# X-Track-ESP32.net
KiCad netlist of a schematic drawn in Altium Designer
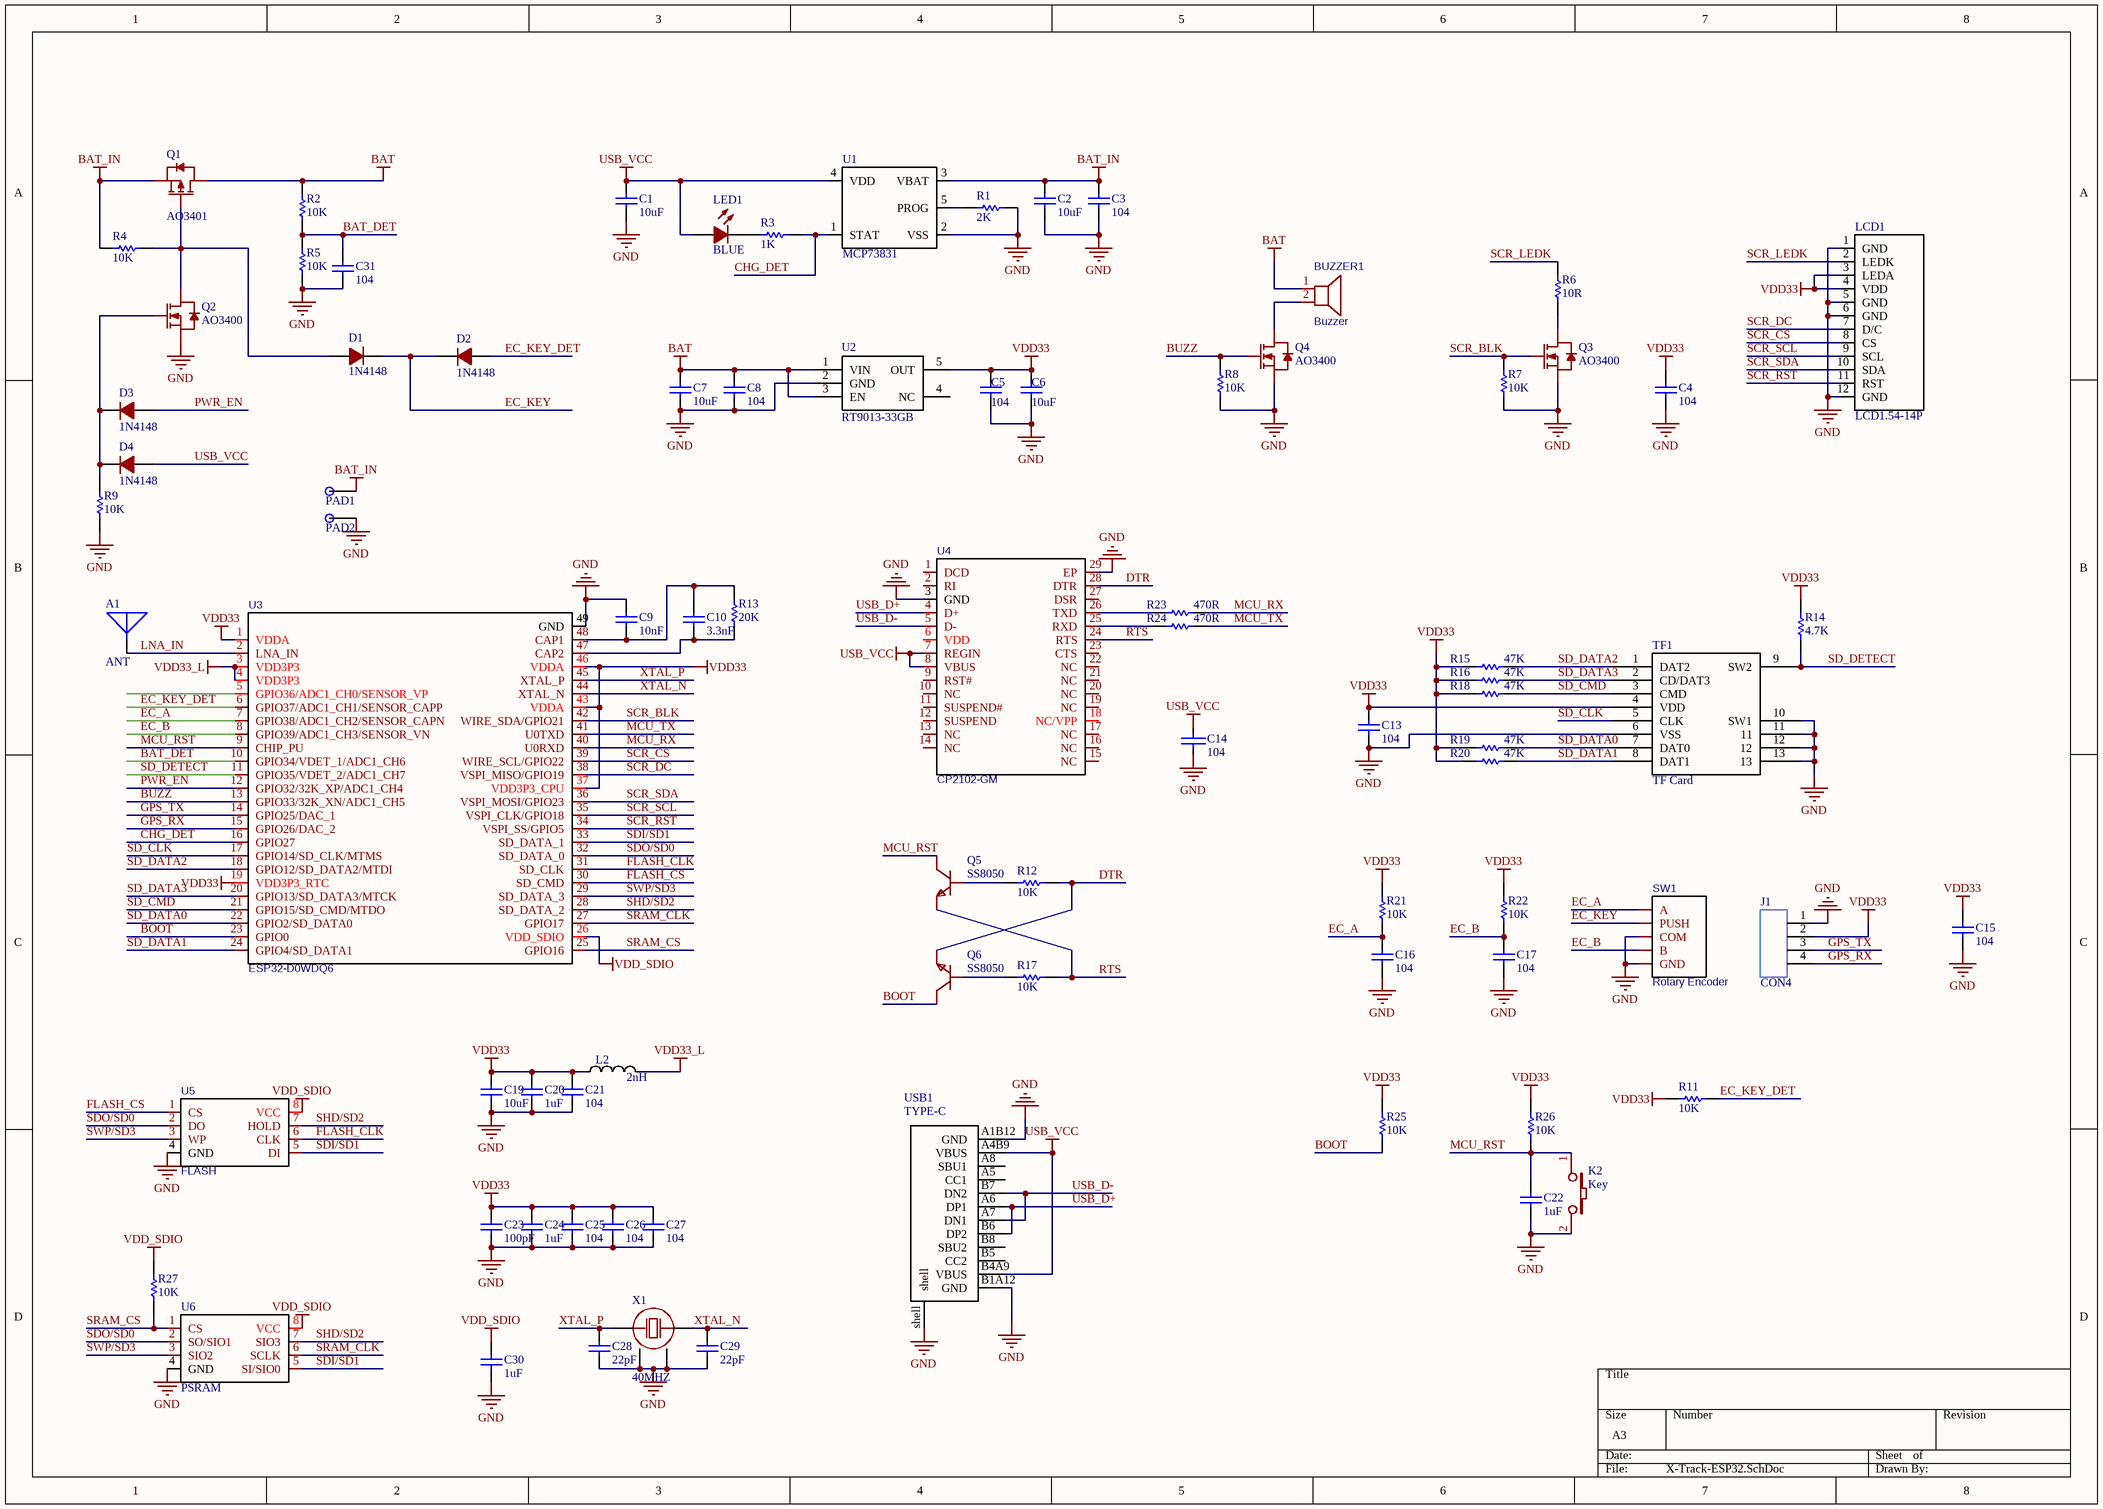
[diagram p0: X-Track-ESP32.SchDoc]

(export (version "E")
  (design (tool "Eeschema 10.0.6"))
  (components
    (comp (ref "A1") (value "ANT") (footprint "ANT-Rainsun-AN5120") (libsource (lib "mylib") (part "ANT")))
    (comp (ref "BUZZER1")
      (value "Buzzer")
      (footprint "BUZZ-SMD_5020")
      (fields
        (field (name "BOM_SUPPLIER PART") "C360618")
        (field (name "BOM_MANUFACTURER PART") "SFN-1207PA6.5")
        (field (name "CONTRIBUTOR") "LCSC")
      )
      (libsource (lib "mylib") (part "Buzzer"))
    )
    (comp (ref "C1") (value "10uF") (footprint "C 0402") (libsource (lib "Sheet") (part "CAP")))
    (comp (ref "C2") (value "10uF") (footprint "C 0402") (libsource (lib "Sheet") (part "CAP")))
    (comp (ref "C3") (value "104") (footprint "C 0402") (libsource (lib "Sheet") (part "CAP")))
    (comp (ref "C4") (value "104") (footprint "C 0402") (libsource (lib "mylib") (part "CAP")))
    (comp (ref "C5") (value "104") (footprint "C 0402") (libsource (lib "Sheet") (part "CAP")))
    (comp (ref "C6") (value "10uF") (footprint "C 0402") (libsource (lib "Sheet") (part "CAP")))
    (comp (ref "C7") (value "10uF") (footprint "C 0402") (libsource (lib "Sheet") (part "CAP")))
    (comp (ref "C8") (value "104") (footprint "C 0402") (libsource (lib "Sheet") (part "CAP")))
    (comp (ref "C9") (value "10nF") (footprint "C 0402") (libsource (lib "mylib") (part "CAP")))
    (comp (ref "C10") (value "3.3nF") (footprint "C 0402") (libsource (lib "mylib") (part "CAP")))
    (comp (ref "C13")
      (value "104")
      (footprint "C 0402")
      (description "Capacitor")
      (libsource (lib "Miscellaneous Devices") (part "Cap"))
    )
    (comp (ref "C14")
      (value "104")
      (footprint "C 0402")
      (description "Capacitor")
      (libsource (lib "*") (part "CAP"))
    )
    (comp (ref "C15") (value "104") (footprint "C 0402") (libsource (lib "mylib") (part "CAP")))
    (comp (ref "C16")
      (value "104")
      (footprint "C 0402")
      (description "Capacitor")
      (libsource (lib "Miscellaneous Devices") (part "Cap"))
    )
    (comp (ref "C17")
      (value "104")
      (footprint "C 0402")
      (description "Capacitor")
      (libsource (lib "Miscellaneous Devices") (part "Cap"))
    )
    (comp (ref "C19") (value "10uF") (footprint "C 0402") (libsource (lib "mylib") (part "CAP")))
    (comp (ref "C20") (value "1uF") (footprint "C 0402") (libsource (lib "mylib") (part "CAP")))
    (comp (ref "C21") (value "104") (footprint "C 0402") (libsource (lib "mylib") (part "CAP")))
    (comp (ref "C22")
      (value "1uF")
      (footprint "C 0402")
      (description "Capacitor")
      (libsource (lib "Miscellaneous Devices") (part "Cap"))
    )
    (comp (ref "C23") (value "100pF") (footprint "C 0402") (libsource (lib "mylib") (part "CAP")))
    (comp (ref "C24") (value "1uF") (footprint "C 0402") (libsource (lib "mylib") (part "CAP")))
    (comp (ref "C25") (value "104") (footprint "C 0402") (libsource (lib "mylib") (part "CAP")))
    (comp (ref "C26") (value "104") (footprint "C 0402") (libsource (lib "mylib") (part "CAP")))
    (comp (ref "C27") (value "104") (footprint "C 0402") (libsource (lib "mylib") (part "CAP")))
    (comp (ref "C28") (value "22pF") (footprint "C 0402") (libsource (lib "mylib") (part "CAP")))
    (comp (ref "C29") (value "22pF") (footprint "C 0402") (libsource (lib "mylib") (part "CAP")))
    (comp (ref "C30") (value "1uF") (footprint "C 0402") (libsource (lib "mylib") (part "CAP")))
    (comp (ref "C31") (value "104") (footprint "C 0402") (libsource (lib "Sheet") (part "CAP")))
    (comp (ref "D1") (value "1N4148") (footprint "SOD523") (libsource (lib "mylib") (part "Diode")))
    (comp (ref "D2") (value "1N4148") (footprint "SOD523") (libsource (lib "mylib") (part "Diode")))
    (comp (ref "D3") (value "1N4148") (footprint "SOD523") (libsource (lib "mylib") (part "Diode")))
    (comp (ref "D4") (value "1N4148") (footprint "SOD523") (libsource (lib "mylib") (part "Diode")))
    (comp (ref "J1") (value "CON4") (footprint "GPS-HTZN") (libsource (lib "mylib") (part "CON4")))
    (comp (ref "K2") (value "Key") (footprint "SW-SMD_3*4") (libsource (lib "mylib") (part "Key")))
    (comp (ref "L2") (value "2nH") (footprint "L 0402") (libsource (lib "mylib") (part "Inductor")))
    (comp (ref "LCD1")
      (value "LCD1.54-14P")
      (footprint "ZJY154T-PG04 FPC 0.7MM")
      (libsource (lib "mylib") (part "LCD1.54-14P_1"))
    )
    (comp (ref "LED1") (value "BLUE") (footprint "LED 0603") (libsource (lib "mylib") (part "LED")))
    (comp (ref "PAD1") (value "PAD") (footprint "PAD") (libsource (lib "mylib") (part "PAD")))
    (comp (ref "PAD2") (value "PAD") (footprint "PAD") (libsource (lib "mylib") (part "PAD")))
    (comp (ref "Q1") (value "AO3401") (footprint "SOT-23") (libsource (lib "mylib") (part "PMOS")))
    (comp (ref "Q2") (value "AO3400") (footprint "SOT-23") (libsource (lib "mylib") (part "NMOS")))
    (comp (ref "Q3") (value "AO3400") (footprint "SOT-23") (libsource (lib "mylib") (part "NMOS")))
    (comp (ref "Q4") (value "AO3400") (footprint "SOT-23") (libsource (lib "mylib") (part "NMOS")))
    (comp (ref "Q5") (value "SS8050") (footprint "SOT-23") (libsource (lib "mylib") (part "NPN")))
    (comp (ref "Q6") (value "SS8050") (footprint "SOT-23") (libsource (lib "mylib") (part "NPN")))
    (comp (ref "R1") (value "2K") (footprint "R 0402") (libsource (lib "Sheet") (part "RES")))
    (comp (ref "R2") (value "10K") (footprint "R 0402") (libsource (lib "mylib") (part "RES")))
    (comp (ref "R3") (value "1K") (footprint "R 0402") (libsource (lib "Sheet") (part "RES")))
    (comp (ref "R4") (value "10K") (footprint "R 0402") (libsource (lib "mylib") (part "RES")))
    (comp (ref "R5") (value "10K") (footprint "R 0402") (libsource (lib "mylib") (part "RES")))
    (comp (ref "R6") (value "10R") (footprint "R 0402") (libsource (lib "Sheet") (part "RES")))
    (comp (ref "R7") (value "10K") (footprint "R 0402") (libsource (lib "Sheet") (part "RES")))
    (comp (ref "R8") (value "10K") (footprint "R 0402") (libsource (lib "Sheet") (part "RES")))
    (comp (ref "R9") (value "10K") (footprint "R 0402") (libsource (lib "mylib") (part "RES")))
    (comp (ref "R11") (value "10K") (footprint "R 0402") (libsource (lib "Sheet") (part "RES")))
    (comp (ref "R12") (value "10K") (footprint "R 0402") (libsource (lib "Sheet") (part "RES")))
    (comp (ref "R13") (value "20K") (footprint "R 0402") (libsource (lib "mylib") (part "RES")))
    (comp (ref "R14") (value "4.7K") (footprint "R 0402") (libsource (lib "Sheet") (part "RES")))
    (comp (ref "R15") (value "47K") (footprint "R 0402") (libsource (lib "Sheet") (part "RES")))
    (comp (ref "R16") (value "47K") (footprint "R 0402") (libsource (lib "Sheet") (part "RES")))
    (comp (ref "R17") (value "10K") (footprint "R 0402") (libsource (lib "Sheet") (part "RES")))
    (comp (ref "R18") (value "47K") (footprint "R 0402") (libsource (lib "Sheet") (part "RES")))
    (comp (ref "R19") (value "47K") (footprint "R 0402") (libsource (lib "Sheet") (part "RES")))
    (comp (ref "R20") (value "47K") (footprint "R 0402") (libsource (lib "Sheet") (part "RES")))
    (comp (ref "R21") (value "10K") (footprint "R 0402") (libsource (lib "Sheet") (part "RES")))
    (comp (ref "R22") (value "10K") (footprint "R 0402") (libsource (lib "Sheet") (part "RES")))
    (comp (ref "R23") (value "470R") (footprint "R 0402") (libsource (lib "Sheet") (part "RES")))
    (comp (ref "R24") (value "470R") (footprint "R 0402") (libsource (lib "Sheet") (part "RES")))
    (comp (ref "R25") (value "10K") (footprint "R 0402") (libsource (lib "Sheet") (part "RES")))
    (comp (ref "R26") (value "10K") (footprint "R 0402") (libsource (lib "Sheet") (part "RES")))
    (comp (ref "R27") (value "10K") (footprint "R 0402") (libsource (lib "mylib") (part "RES")))
    (comp (ref "SW1")
      (value "Rotary Encoder")
      (footprint "SIQ-02FVS3")
      (fields
        (field (name "BOM_SUPPLIER PART") "C1322543")
        (field (name "BOM_MANUFACTURER PART") "EC11E1534443")
        (field (name "CONTRIBUTOR") "LCSC")
      )
      (libsource (lib "mylib") (part "Rotary Encoder"))
    )
    (comp (ref "TF1") (value "TF Card") (footprint "TF-Card") (libsource (lib "mylib") (part "TF Card")))
    (comp (ref "U1") (value "MCP73831") (footprint "SOT23-5") (libsource (lib "mylib") (part "MCP73831")))
    (comp (ref "U2") (value "RT9013-33GB") (footprint "SOT23-5") (libsource (lib "mylib") (part "SPX3819")))
    (comp (ref "U3")
      (value "ESP32-D0WDQ6")
      (footprint "QFN-48")
      (fields (field (name "BOM_SUPPLIER PART") "C129733") (field (name "CONTRIBUTOR") "LCSC"))
      (libsource (lib "mylib") (part "ESP32-D0WDQ6"))
    )
    (comp (ref "U4")
      (value "CP2102-GM")
      (footprint "QFN-28")
      (fields (field (name "BOM_SUPPLIER PART") "C430012") (field (name "CONTRIBUTOR") "LCSC"))
      (libsource (lib "mylib") (part "CP2102-GM"))
    )
    (comp (ref "U5")
      (value "FLASH")
      (footprint "SOIC-8")
      (fields
        (field (name "BOM_SUPPLIER PART") "C179173")
        (field (name "BOM_MANUFACTURER PART") "W25Q32JVSSIQ")
        (field (name "CONTRIBUTOR") "LCSC")
      )
      (libsource (lib "mylib") (part "FLASH"))
    )
    (comp (ref "U6") (value "PSRAM") (footprint "SOP-8") (libsource (lib "mylib") (part "PSRAM")))
    (comp (ref "USB1")
      (value "TYPE-C")
      (footprint "USB-TYPE-C")
      (description "TYPE-C 16pin")
      (libsource (lib "Sheet") (part "USB TYPE-C"))
    )
    (comp (ref "X1") (value "40MHZ") (footprint "SMD-3225") (libsource (lib "mylib") (part "XTAL-4P")))
  )
  (nets
    (net (code "1") (name "/BAT_DET") (class "Default")
      (node (ref "C31") (pin "2") (pinfunction "2_2") (pintype "passive"))
      (node (ref "R2") (pin "1") (pinfunction "1_1") (pintype "passive"))
      (node (ref "R5") (pin "2") (pinfunction "2_2") (pintype "passive"))
      (node (ref "U3") (pin "10") (pinfunction "GPIO34/VDET_1/ADC1_CH6_10") (pintype "passive"))
    )
    (net (code "2") (name "/BOOT") (class "Default")
      (node (ref "Q6") (pin "3") (pinfunction "C_3") (pintype "passive"))
      (node (ref "R25") (pin "2") (pinfunction "2_2") (pintype "passive"))
      (node (ref "U3") (pin "23") (pinfunction "GPIO0_23") (pintype "passive"))
    )
    (net (code "3") (name "/BUZZ") (class "Default")
      (node (ref "Q4") (pin "1") (pinfunction "G_1") (pintype "passive"))
      (node (ref "R8") (pin "1") (pinfunction "1_1") (pintype "passive"))
      (node (ref "U3") (pin "13") (pinfunction "GPIO33/32K_XN/ADC1_CH5_13") (pintype "passive"))
    )
    (net (code "4") (name "/CHG_DET") (class "Default")
      (node (ref "R3") (pin "1") (pinfunction "1_1") (pintype "passive"))
      (node (ref "U1") (pin "1") (pinfunction "STAT_1") (pintype "passive"))
      (node (ref "U3") (pin "16") (pinfunction "GPIO27_16") (pintype "passive"))
    )
    (net (code "5") (name "/DTR") (class "Default")
      (node (ref "Q6") (pin "2") (pinfunction "E_2") (pintype "passive"))
      (node (ref "R12") (pin "1") (pinfunction "1_1") (pintype "passive"))
      (node (ref "U4") (pin "28") (pinfunction "DTR_28") (pintype "passive"))
    )
    (net (code "6") (name "/EC_A") (class "Default")
      (node (ref "C16") (pin "1") (pinfunction "1_1") (pintype "passive"))
      (node (ref "R21") (pin "2") (pinfunction "2_2") (pintype "passive"))
      (node (ref "SW1") (pin "1") (pinfunction "A_1") (pintype "passive"))
      (node (ref "U3") (pin "7") (pinfunction "GPIO38/ADC1_CH2/SENSOR_CAPN_7") (pintype "passive"))
    )
    (net (code "7") (name "/EC_B") (class "Default")
      (node (ref "C17") (pin "1") (pinfunction "1_1") (pintype "passive"))
      (node (ref "R22") (pin "2") (pinfunction "2_2") (pintype "passive"))
      (node (ref "SW1") (pin "4") (pinfunction "B_4") (pintype "passive"))
      (node (ref "U3") (pin "8") (pinfunction "GPIO39/ADC1_CH3/SENSOR_VN_8") (pintype "passive"))
    )
    (net (code "8") (name "/EC_KEY") (class "Default")
      (node (ref "D1") (pin "2") (pinfunction "C_2") (pintype "passive"))
      (node (ref "D2") (pin "2") (pinfunction "C_2") (pintype "passive"))
      (node (ref "SW1") (pin "2") (pinfunction "PUSH_2") (pintype "passive"))
    )
    (net (code "9") (name "/EC_KEY_DET") (class "Default")
      (node (ref "D2") (pin "1") (pinfunction "A_1") (pintype "passive"))
      (node (ref "R11") (pin "2") (pinfunction "2_2") (pintype "passive"))
      (node (ref "U3") (pin "6") (pinfunction "GPIO37/ADC1_CH1/SENSOR_CAPP_6") (pintype "passive"))
    )
    (net (code "10") (name "/FLASH_CLK") (class "Default")
      (node (ref "U3") (pin "31") (pinfunction "SD_CLK_31") (pintype "passive"))
      (node (ref "U5") (pin "6") (pinfunction "CLK_6") (pintype "passive"))
    )
    (net (code "11") (name "/FLASH_CS") (class "Default")
      (node (ref "U3") (pin "30") (pinfunction "SD_CMD_30") (pintype "passive"))
      (node (ref "U5") (pin "1") (pinfunction "CS_1") (pintype "passive"))
    )
    (net (code "12") (name "/GPS_RX") (class "Default")
      (node (ref "J1") (pin "4") (pinfunction "4_4") (pintype "passive"))
      (node (ref "U3") (pin "15") (pinfunction "GPIO26/DAC_2_15") (pintype "passive"))
    )
    (net (code "13") (name "/GPS_TX") (class "Default")
      (node (ref "J1") (pin "3") (pinfunction "3_3") (pintype "passive"))
      (node (ref "U3") (pin "14") (pinfunction "GPIO25/DAC_1_14") (pintype "passive"))
    )
    (net (code "14") (name "/LNA_IN") (class "Default")
      (node (ref "A1") (pin "1") (pinfunction "1_1") (pintype "passive"))
      (node (ref "U3") (pin "2") (pinfunction "LNA_IN_2") (pintype "passive"))
    )
    (net (code "15") (name "/MCU_RST") (class "Default")
      (node (ref "C22") (pin "1") (pinfunction "1_1") (pintype "passive"))
      (node (ref "K2") (pin "1") (pinfunction "1_1") (pintype "passive"))
      (node (ref "Q5") (pin "3") (pinfunction "C_3") (pintype "passive"))
      (node (ref "R26") (pin "2") (pinfunction "2_2") (pintype "passive"))
      (node (ref "U3") (pin "9") (pinfunction "CHIP_PU_9") (pintype "passive"))
    )
    (net (code "16") (name "/MCU_RX") (class "Default")
      (node (ref "R23") (pin "2") (pinfunction "2_2") (pintype "passive"))
      (node (ref "U3") (pin "40") (pinfunction "U0RXD_40") (pintype "passive"))
    )
    (net (code "17") (name "/MCU_TX") (class "Default")
      (node (ref "R24") (pin "2") (pinfunction "2_2") (pintype "passive"))
      (node (ref "U3") (pin "41") (pinfunction "U0TXD_41") (pintype "passive"))
    )
    (net (code "18") (name "/PWR_EN") (class "Default")
      (node (ref "D3") (pin "1") (pinfunction "A_1") (pintype "passive"))
      (node (ref "U3") (pin "12") (pinfunction "GPIO32/32K_XP/ADC1_CH4_12") (pintype "passive"))
    )
    (net (code "19") (name "/RTS") (class "Default")
      (node (ref "Q5") (pin "2") (pinfunction "E_2") (pintype "passive"))
      (node (ref "R17") (pin "1") (pinfunction "1_1") (pintype "passive"))
      (node (ref "U4") (pin "24") (pinfunction "RTS_24") (pintype "passive"))
    )
    (net (code "20") (name "/SCR_BLK") (class "Default")
      (node (ref "Q3") (pin "1") (pinfunction "G_1") (pintype "passive"))
      (node (ref "R7") (pin "1") (pinfunction "1_1") (pintype "passive"))
      (node (ref "U3") (pin "42") (pinfunction "WIRE_SDA/GPIO21_42") (pintype "passive"))
    )
    (net (code "21") (name "/SCR_CS") (class "Default")
      (node (ref "LCD1") (pin "8") (pinfunction "CS_8") (pintype "passive"))
      (node (ref "U3") (pin "39") (pinfunction "WIRE_SCL/GPIO22_39") (pintype "passive"))
    )
    (net (code "22") (name "/SCR_DC") (class "Default")
      (node (ref "LCD1") (pin "7") (pinfunction "D/C_7") (pintype "passive"))
      (node (ref "U3") (pin "38") (pinfunction "VSPI_MISO/GPIO19_38") (pintype "passive"))
    )
    (net (code "23") (name "/SCR_LEDK") (class "Default")
      (node (ref "LCD1") (pin "2") (pinfunction "LEDK_2") (pintype "passive"))
      (node (ref "R6") (pin "2") (pinfunction "2_2") (pintype "passive"))
    )
    (net (code "24") (name "/SCR_RST") (class "Default")
      (node (ref "LCD1") (pin "11") (pinfunction "RST_11") (pintype "passive"))
      (node (ref "U3") (pin "34") (pinfunction "VSPI_SS/GPIO5_34") (pintype "passive"))
    )
    (net (code "25") (name "/SCR_SCL") (class "Default")
      (node (ref "LCD1") (pin "9") (pinfunction "SCL_9") (pintype "passive"))
      (node (ref "U3") (pin "35") (pinfunction "VSPI_CLK/GPIO18_35") (pintype "passive"))
    )
    (net (code "26") (name "/SCR_SDA") (class "Default")
      (node (ref "LCD1") (pin "10") (pinfunction "SDA_10") (pintype "passive"))
      (node (ref "U3") (pin "36") (pinfunction "VSPI_MOSI/GPIO23_36") (pintype "passive"))
    )
    (net (code "27") (name "/SDI{slash}SD1") (class "Default")
      (node (ref "U3") (pin "33") (pinfunction "SD_DATA_1_33") (pintype "passive"))
      (node (ref "U5") (pin "5") (pinfunction "DI_5") (pintype "passive"))
      (node (ref "U6") (pin "5") (pinfunction "SI/SIO0_5") (pintype "passive"))
    )
    (net (code "28") (name "/SDO{slash}SD0") (class "Default")
      (node (ref "U3") (pin "32") (pinfunction "SD_DATA_0_32") (pintype "passive"))
      (node (ref "U5") (pin "2") (pinfunction "DO_2") (pintype "passive"))
      (node (ref "U6") (pin "2") (pinfunction "SO/SIO1_2") (pintype "passive"))
    )
    (net (code "29") (name "/SD_CLK") (class "Default")
      (node (ref "TF1") (pin "5") (pinfunction "CLK_5") (pintype "passive"))
      (node (ref "U3") (pin "17") (pinfunction "GPIO14/SD_CLK/MTMS_17") (pintype "passive"))
    )
    (net (code "30") (name "/SD_CMD") (class "Default")
      (node (ref "R18") (pin "2") (pinfunction "2_2") (pintype "passive"))
      (node (ref "TF1") (pin "3") (pinfunction "CMD_3") (pintype "passive"))
      (node (ref "U3") (pin "21") (pinfunction "GPIO15/SD_CMD/MTDO_21") (pintype "passive"))
    )
    (net (code "31") (name "/SD_DATA0") (class "Default")
      (node (ref "R19") (pin "2") (pinfunction "2_2") (pintype "passive"))
      (node (ref "TF1") (pin "7") (pinfunction "DAT0_7") (pintype "passive"))
      (node (ref "U3") (pin "22") (pinfunction "GPIO2/SD_DATA0_22") (pintype "passive"))
    )
    (net (code "32") (name "/SD_DATA1") (class "Default")
      (node (ref "R20") (pin "2") (pinfunction "2_2") (pintype "passive"))
      (node (ref "TF1") (pin "8") (pinfunction "DAT1_8") (pintype "passive"))
      (node (ref "U3") (pin "24") (pinfunction "GPIO4/SD_DATA1_24") (pintype "passive"))
    )
    (net (code "33") (name "/SD_DATA2") (class "Default")
      (node (ref "R15") (pin "2") (pinfunction "2_2") (pintype "passive"))
      (node (ref "TF1") (pin "1") (pinfunction "DAT2_1") (pintype "passive"))
      (node (ref "U3") (pin "18") (pinfunction "GPIO12/SD_DATA2/MTDI_18") (pintype "passive"))
    )
    (net (code "34") (name "/SD_DATA3") (class "Default")
      (node (ref "R16") (pin "2") (pinfunction "2_2") (pintype "passive"))
      (node (ref "TF1") (pin "2") (pinfunction "CD/DAT3_2") (pintype "passive"))
      (node (ref "U3") (pin "20") (pinfunction "GPIO13/SD_DATA3/MTCK_20") (pintype "passive"))
    )
    (net (code "35") (name "/SD_DETECT") (class "Default")
      (node (ref "R14") (pin "1") (pinfunction "1_1") (pintype "passive"))
      (node (ref "TF1") (pin "9") (pinfunction "SW2_9") (pintype "passive"))
      (node (ref "U3") (pin "11") (pinfunction "GPIO35/VDET_2/ADC1_CH7_11") (pintype "passive"))
    )
    (net (code "36") (name "/SHD{slash}SD2") (class "Default")
      (node (ref "U3") (pin "28") (pinfunction "SD_DATA_2_28") (pintype "passive"))
      (node (ref "U5") (pin "7") (pinfunction "HOLD_7") (pintype "passive"))
      (node (ref "U6") (pin "7") (pinfunction "SIO3_7") (pintype "passive"))
    )
    (net (code "37") (name "/SRAM_CLK") (class "Default")
      (node (ref "U3") (pin "27") (pinfunction "GPIO17_27") (pintype "passive"))
      (node (ref "U6") (pin "6") (pinfunction "SCLK_6") (pintype "passive"))
    )
    (net (code "38") (name "/SRAM_CS") (class "Default")
      (node (ref "R27") (pin "2") (pinfunction "2_2") (pintype "passive"))
      (node (ref "U3") (pin "25") (pinfunction "GPIO16_25") (pintype "passive"))
      (node (ref "U6") (pin "1") (pinfunction "CS_1") (pintype "passive"))
    )
    (net (code "39") (name "/SWP{slash}SD3") (class "Default")
      (node (ref "U3") (pin "29") (pinfunction "SD_DATA_3_29") (pintype "passive"))
      (node (ref "U5") (pin "3") (pinfunction "WP_3") (pintype "passive"))
      (node (ref "U6") (pin "3") (pinfunction "SIO2_3") (pintype "passive"))
    )
    (net (code "40") (name "/USB_D+") (class "Default")
      (node (ref "U4") (pin "4") (pinfunction "D+_4") (pintype "passive"))
      (node (ref "USB1") (pin "A6") (pinfunction "DP1_A6") (pintype "passive"))
      (node (ref "USB1") (pin "B6") (pinfunction "DP2_B6") (pintype "passive"))
    )
    (net (code "41") (name "/USB_D-") (class "Default")
      (node (ref "U4") (pin "5") (pinfunction "D-_5") (pintype "passive"))
      (node (ref "USB1") (pin "A7") (pinfunction "DN1_A7") (pintype "passive"))
      (node (ref "USB1") (pin "B7") (pinfunction "DN2_B7") (pintype "passive"))
    )
    (net (code "42") (name "/XTAL_N") (class "Default")
      (node (ref "C29") (pin "1") (pinfunction "1_1") (pintype "passive"))
      (node (ref "U3") (pin "44") (pinfunction "XTAL_N_44") (pintype "passive"))
      (node (ref "X1") (pin "3") (pinfunction "3_3") (pintype "passive"))
    )
    (net (code "43") (name "/XTAL_P") (class "Default")
      (node (ref "C28") (pin "2") (pinfunction "2_2") (pintype "passive"))
      (node (ref "U3") (pin "45") (pinfunction "XTAL_P_45") (pintype "passive"))
      (node (ref "X1") (pin "1") (pinfunction "1_1") (pintype "passive"))
    )
    (net (code "44") (name "BAT") (class "Default")
      (node (ref "BUZZER1") (pin "1") (pinfunction "1_1") (pintype "passive"))
      (node (ref "C7") (pin "2") (pinfunction "2_2") (pintype "passive"))
      (node (ref "C8") (pin "2") (pinfunction "2_2") (pintype "passive"))
      (node (ref "Q1") (pin "3") (pinfunction "D_3") (pintype "passive"))
      (node (ref "R2") (pin "2") (pinfunction "2_2") (pintype "passive"))
      (node (ref "U2") (pin "1") (pinfunction "VIN_1") (pintype "passive"))
      (node (ref "U2") (pin "3") (pinfunction "EN_3") (pintype "passive"))
    )
    (net (code "45") (name "BAT_IN") (class "Default")
      (node (ref "C2") (pin "2") (pinfunction "2_2") (pintype "passive"))
      (node (ref "C3") (pin "2") (pinfunction "2_2") (pintype "passive"))
      (node (ref "PAD1") (pin "1") (pinfunction "TP_1") (pintype "passive"))
      (node (ref "Q1") (pin "2") (pinfunction "S_2") (pintype "passive"))
      (node (ref "R4") (pin "2") (pinfunction "2_2") (pintype "passive"))
      (node (ref "U1") (pin "3") (pinfunction "VBAT_3") (pintype "passive"))
    )
    (net (code "46") (name "GND") (class "Default")
      (node (ref "C1") (pin "1") (pinfunction "1_1") (pintype "passive"))
      (node (ref "C13") (pin "2") (pinfunction "2_2") (pintype "passive"))
      (node (ref "C14") (pin "1") (pinfunction "1_1") (pintype "passive"))
      (node (ref "C15") (pin "1") (pinfunction "1_1") (pintype "passive"))
      (node (ref "C16") (pin "2") (pinfunction "2_2") (pintype "passive"))
      (node (ref "C17") (pin "2") (pinfunction "2_2") (pintype "passive"))
      (node (ref "C19") (pin "1") (pinfunction "1_1") (pintype "passive"))
      (node (ref "C2") (pin "1") (pinfunction "1_1") (pintype "passive"))
      (node (ref "C20") (pin "1") (pinfunction "1_1") (pintype "passive"))
      (node (ref "C21") (pin "1") (pinfunction "1_1") (pintype "passive"))
      (node (ref "C22") (pin "2") (pinfunction "2_2") (pintype "passive"))
      (node (ref "C23") (pin "1") (pinfunction "1_1") (pintype "passive"))
      (node (ref "C24") (pin "1") (pinfunction "1_1") (pintype "passive"))
      (node (ref "C25") (pin "1") (pinfunction "1_1") (pintype "passive"))
      (node (ref "C26") (pin "1") (pinfunction "1_1") (pintype "passive"))
      (node (ref "C27") (pin "1") (pinfunction "1_1") (pintype "passive"))
      (node (ref "C28") (pin "1") (pinfunction "1_1") (pintype "passive"))
      (node (ref "C29") (pin "2") (pinfunction "2_2") (pintype "passive"))
      (node (ref "C3") (pin "1") (pinfunction "1_1") (pintype "passive"))
      (node (ref "C30") (pin "1") (pinfunction "1_1") (pintype "passive"))
      (node (ref "C31") (pin "1") (pinfunction "1_1") (pintype "passive"))
      (node (ref "C4") (pin "1") (pinfunction "1_1") (pintype "passive"))
      (node (ref "C5") (pin "1") (pinfunction "1_1") (pintype "passive"))
      (node (ref "C6") (pin "1") (pinfunction "1_1") (pintype "passive"))
      (node (ref "C7") (pin "1") (pinfunction "1_1") (pintype "passive"))
      (node (ref "C8") (pin "1") (pinfunction "1_1") (pintype "passive"))
      (node (ref "C9") (pin "2") (pinfunction "2_2") (pintype "passive"))
      (node (ref "J1") (pin "1") (pinfunction "1_1") (pintype "passive"))
      (node (ref "K2") (pin "2") (pinfunction "2_2") (pintype "passive"))
      (node (ref "LCD1") (pin "1") (pinfunction "GND_1") (pintype "passive"))
      (node (ref "LCD1") (pin "12") (pinfunction "GND_12") (pintype "passive"))
      (node (ref "LCD1") (pin "5") (pinfunction "GND_5") (pintype "passive"))
      (node (ref "LCD1") (pin "6") (pinfunction "GND_6") (pintype "passive"))
      (node (ref "PAD2") (pin "1") (pinfunction "TP_1") (pintype "passive"))
      (node (ref "Q2") (pin "2") (pinfunction "S_2") (pintype "passive"))
      (node (ref "Q3") (pin "2") (pinfunction "S_2") (pintype "passive"))
      (node (ref "Q4") (pin "2") (pinfunction "S_2") (pintype "passive"))
      (node (ref "R1") (pin "1") (pinfunction "1_1") (pintype "passive"))
      (node (ref "R5") (pin "1") (pinfunction "1_1") (pintype "passive"))
      (node (ref "R7") (pin "2") (pinfunction "2_2") (pintype "passive"))
      (node (ref "R8") (pin "2") (pinfunction "2_2") (pintype "passive"))
      (node (ref "R9") (pin "1") (pinfunction "1_1") (pintype "passive"))
      (node (ref "SW1") (pin "3") (pinfunction "COM_3") (pintype "passive"))
      (node (ref "SW1") (pin "5") (pinfunction "GND_5") (pintype "passive"))
      (node (ref "TF1") (pin "10") (pinfunction "SW1_10") (pintype "passive"))
      (node (ref "TF1") (pin "11") (pinfunction "11_11") (pintype "passive"))
      (node (ref "TF1") (pin "12") (pinfunction "12_12") (pintype "passive"))
      (node (ref "TF1") (pin "13") (pinfunction "13_13") (pintype "passive"))
      (node (ref "TF1") (pin "6") (pinfunction "VSS_6") (pintype "passive"))
      (node (ref "U1") (pin "2") (pinfunction "VSS_2") (pintype "passive"))
      (node (ref "U2") (pin "2") (pinfunction "GND_2") (pintype "passive"))
      (node (ref "U3") (pin "49") (pinfunction "GND_49") (pintype "passive"))
      (node (ref "U4") (pin "29") (pinfunction "EP_29") (pintype "passive"))
      (node (ref "U4") (pin "3") (pinfunction "GND_3") (pintype "passive"))
      (node (ref "U5") (pin "4") (pinfunction "GND_4") (pintype "passive"))
      (node (ref "U6") (pin "4") (pinfunction "GND_4") (pintype "passive"))
      (node (ref "USB1") (pin "A1B12") (pinfunction "GND_A1B12") (pintype "passive"))
      (node (ref "USB1") (pin "B1A12") (pinfunction "GND_B1A12") (pintype "passive"))
      (node (ref "USB1") (pin "shell") (pinfunction "shell_shell") (pintype "passive"))
      (node (ref "X1") (pin "2") (pinfunction "2_2") (pintype "passive"))
      (node (ref "X1") (pin "4") (pinfunction "4_4") (pintype "passive"))
    )
    (net (code "47") (name "Net-(D1-A)") (class "Default")
      (node (ref "D1") (pin "1") (pinfunction "A_1") (pintype "passive"))
      (node (ref "Q1") (pin "1") (pinfunction "G_1") (pintype "passive"))
      (node (ref "Q2") (pin "3") (pinfunction "D_3") (pintype "passive"))
      (node (ref "R4") (pin "1") (pinfunction "1_1") (pintype "passive"))
    )
    (net (code "48") (name "Net-(D3-C)") (class "Default")
      (node (ref "D3") (pin "2") (pinfunction "C_2") (pintype "passive"))
      (node (ref "D4") (pin "2") (pinfunction "C_2") (pintype "passive"))
      (node (ref "Q2") (pin "1") (pinfunction "G_1") (pintype "passive"))
      (node (ref "R9") (pin "2") (pinfunction "2_2") (pintype "passive"))
    )
    (net (code "49") (name "Net-(LED1-C)") (class "Default")
      (node (ref "LED1") (pin "2") (pinfunction "C_2") (pintype "passive"))
      (node (ref "R3") (pin "2") (pinfunction "2_2") (pintype "passive"))
    )
    (net (code "50") (name "Net-(Q3-D)") (class "Default")
      (node (ref "Q3") (pin "3") (pinfunction "D_3") (pintype "passive"))
      (node (ref "R6") (pin "1") (pinfunction "1_1") (pintype "passive"))
    )
    (net (code "51") (name "Net-(Q4-D)") (class "Default")
      (node (ref "BUZZER1") (pin "2") (pinfunction "2_2") (pintype "passive"))
      (node (ref "Q4") (pin "3") (pinfunction "D_3") (pintype "passive"))
    )
    (net (code "52") (name "Net-(Q5-B)") (class "Default")
      (node (ref "Q5") (pin "1") (pinfunction "B_1") (pintype "passive"))
      (node (ref "R12") (pin "2") (pinfunction "2_2") (pintype "passive"))
    )
    (net (code "53") (name "Net-(Q6-B)") (class "Default")
      (node (ref "Q6") (pin "1") (pinfunction "B_1") (pintype "passive"))
      (node (ref "R17") (pin "2") (pinfunction "2_2") (pintype "passive"))
    )
    (net (code "54") (name "Net-(U1-PROG)") (class "Default")
      (node (ref "R1") (pin "2") (pinfunction "2_2") (pintype "passive"))
      (node (ref "U1") (pin "5") (pinfunction "PROG_5") (pintype "passive"))
    )
    (net (code "55") (name "Net-(U3-CAP1)") (class "Default")
      (node (ref "C10") (pin "2") (pinfunction "2_2") (pintype "passive"))
      (node (ref "C9") (pin "1") (pinfunction "1_1") (pintype "passive"))
      (node (ref "R13") (pin "2") (pinfunction "2_2") (pintype "passive"))
      (node (ref "U3") (pin "48") (pinfunction "CAP1_48") (pintype "passive"))
    )
    (net (code "56") (name "Net-(U3-CAP2)") (class "Default")
      (node (ref "C10") (pin "1") (pinfunction "1_1") (pintype "passive"))
      (node (ref "R13") (pin "1") (pinfunction "1_1") (pintype "passive"))
      (node (ref "U3") (pin "47") (pinfunction "CAP2_47") (pintype "passive"))
    )
    (net (code "57") (name "Net-(U4-RXD)") (class "Default")
      (node (ref "R24") (pin "1") (pinfunction "1_1") (pintype "passive"))
      (node (ref "U4") (pin "25") (pinfunction "RXD_25") (pintype "passive"))
    )
    (net (code "58") (name "Net-(U4-TXD)") (class "Default")
      (node (ref "R23") (pin "1") (pinfunction "1_1") (pintype "passive"))
      (node (ref "U4") (pin "26") (pinfunction "TXD_26") (pintype "passive"))
    )
    (net (code "59") (name "USB_VCC") (class "Default")
      (node (ref "C1") (pin "2") (pinfunction "2_2") (pintype "passive"))
      (node (ref "C14") (pin "2") (pinfunction "2_2") (pintype "passive"))
      (node (ref "D4") (pin "1") (pinfunction "A_1") (pintype "passive"))
      (node (ref "LED1") (pin "1") (pinfunction "A_1") (pintype "passive"))
      (node (ref "U1") (pin "4") (pinfunction "VDD_4") (pintype "passive"))
      (node (ref "U4") (pin "7") (pinfunction "REGIN_7") (pintype "passive"))
      (node (ref "U4") (pin "8") (pinfunction "VBUS_8") (pintype "passive"))
      (node (ref "USB1") (pin "A4B9") (pinfunction "VBUS_A4B9") (pintype "passive"))
      (node (ref "USB1") (pin "B4A9") (pinfunction "VBUS_B4A9") (pintype "passive"))
    )
    (net (code "60") (name "VDD33") (class "Default")
      (node (ref "C13") (pin "1") (pinfunction "1_1") (pintype "passive"))
      (node (ref "C15") (pin "2") (pinfunction "2_2") (pintype "passive"))
      (node (ref "C19") (pin "2") (pinfunction "2_2") (pintype "passive"))
      (node (ref "C20") (pin "2") (pinfunction "2_2") (pintype "passive"))
      (node (ref "C21") (pin "2") (pinfunction "2_2") (pintype "passive"))
      (node (ref "C23") (pin "2") (pinfunction "2_2") (pintype "passive"))
      (node (ref "C24") (pin "2") (pinfunction "2_2") (pintype "passive"))
      (node (ref "C25") (pin "2") (pinfunction "2_2") (pintype "passive"))
      (node (ref "C26") (pin "2") (pinfunction "2_2") (pintype "passive"))
      (node (ref "C27") (pin "2") (pinfunction "2_2") (pintype "passive"))
      (node (ref "C4") (pin "2") (pinfunction "2_2") (pintype "passive"))
      (node (ref "C5") (pin "2") (pinfunction "2_2") (pintype "passive"))
      (node (ref "C6") (pin "2") (pinfunction "2_2") (pintype "passive"))
      (node (ref "J1") (pin "2") (pinfunction "2_2") (pintype "passive"))
      (node (ref "L2") (pin "1") (pinfunction "1_1") (pintype "passive"))
      (node (ref "LCD1") (pin "3") (pinfunction "LEDA_3") (pintype "passive"))
      (node (ref "LCD1") (pin "4") (pinfunction "VDD_4") (pintype "passive"))
      (node (ref "R11") (pin "1") (pinfunction "1_1") (pintype "passive"))
      (node (ref "R14") (pin "2") (pinfunction "2_2") (pintype "passive"))
      (node (ref "R15") (pin "1") (pinfunction "1_1") (pintype "passive"))
      (node (ref "R16") (pin "1") (pinfunction "1_1") (pintype "passive"))
      (node (ref "R18") (pin "1") (pinfunction "1_1") (pintype "passive"))
      (node (ref "R19") (pin "1") (pinfunction "1_1") (pintype "passive"))
      (node (ref "R20") (pin "1") (pinfunction "1_1") (pintype "passive"))
      (node (ref "R21") (pin "1") (pinfunction "1_1") (pintype "passive"))
      (node (ref "R22") (pin "1") (pinfunction "1_1") (pintype "passive"))
      (node (ref "R25") (pin "1") (pinfunction "1_1") (pintype "passive"))
      (node (ref "R26") (pin "1") (pinfunction "1_1") (pintype "passive"))
      (node (ref "TF1") (pin "4") (pinfunction "VDD_4") (pintype "passive"))
      (node (ref "U2") (pin "5") (pinfunction "OUT_5") (pintype "passive"))
      (node (ref "U3") (pin "1") (pinfunction "VDDA_1") (pintype "passive"))
      (node (ref "U3") (pin "19") (pinfunction "VDD3P3_RTC_19") (pintype "passive"))
      (node (ref "U3") (pin "37") (pinfunction "VDD3P3_CPU_37") (pintype "passive"))
      (node (ref "U3") (pin "43") (pinfunction "VDDA_43") (pintype "passive"))
      (node (ref "U3") (pin "46") (pinfunction "VDDA_46") (pintype "passive"))
    )
    (net (code "61") (name "VDD33_L") (class "Default")
      (node (ref "L2") (pin "2") (pinfunction "2_2") (pintype "passive"))
      (node (ref "U3") (pin "3") (pinfunction "VDD3P3_3") (pintype "passive"))
      (node (ref "U3") (pin "4") (pinfunction "VDD3P3_4") (pintype "passive"))
    )
    (net (code "62") (name "VDD_SDIO") (class "Default")
      (node (ref "C30") (pin "2") (pinfunction "2_2") (pintype "passive"))
      (node (ref "R27") (pin "1") (pinfunction "1_1") (pintype "passive"))
      (node (ref "U3") (pin "26") (pinfunction "VDD_SDIO_26") (pintype "passive"))
      (node (ref "U5") (pin "8") (pinfunction "VCC_8") (pintype "passive"))
      (node (ref "U6") (pin "8") (pinfunction "VCC_8") (pintype "passive"))
    )
    (net (code "63") (name "unconnected-(U2-NC-Pad4)") (class "Default")
      (node (ref "U2") (pin "4") (pinfunction "NC_4") (pintype "passive"))
    )
    (net (code "64") (name "unconnected-(U3-GPIO36{slash}ADC1_CH0{slash}SENSOR_VP-Pad5)") (class "Default")
      (node (ref "U3") (pin "5") (pinfunction "GPIO36/ADC1_CH0/SENSOR_VP_5") (pintype "passive"))
    )
    (net (code "65") (name "unconnected-(U4-CTS-Pad23)") (class "Default")
      (node (ref "U4") (pin "23") (pinfunction "CTS_23") (pintype "passive"))
    )
    (net (code "66") (name "unconnected-(U4-DCD-Pad1)") (class "Default")
      (node (ref "U4") (pin "1") (pinfunction "DCD_1") (pintype "passive"))
    )
    (net (code "67") (name "unconnected-(U4-DSR-Pad27)") (class "Default")
      (node (ref "U4") (pin "27") (pinfunction "DSR_27") (pintype "passive"))
    )
    (net (code "68") (name "unconnected-(U4-NC-Pad10)") (class "Default")
      (node (ref "U4") (pin "10") (pinfunction "NC_10") (pintype "passive"))
    )
    (net (code "69") (name "unconnected-(U4-NC-Pad13)") (class "Default")
      (node (ref "U4") (pin "13") (pinfunction "NC_13") (pintype "passive"))
    )
    (net (code "70") (name "unconnected-(U4-NC-Pad14)") (class "Default")
      (node (ref "U4") (pin "14") (pinfunction "NC_14") (pintype "passive"))
    )
    (net (code "71") (name "unconnected-(U4-NC-Pad15)") (class "Default")
      (node (ref "U4") (pin "15") (pinfunction "NC_15") (pintype "passive"))
    )
    (net (code "72") (name "unconnected-(U4-NC-Pad16)") (class "Default")
      (node (ref "U4") (pin "16") (pinfunction "NC_16") (pintype "passive"))
    )
    (net (code "73") (name "unconnected-(U4-NC-Pad17)") (class "Default")
      (node (ref "U4") (pin "17") (pinfunction "NC_17") (pintype "passive"))
    )
    (net (code "74") (name "unconnected-(U4-NC-Pad19)") (class "Default")
      (node (ref "U4") (pin "19") (pinfunction "NC_19") (pintype "passive"))
    )
    (net (code "75") (name "unconnected-(U4-NC-Pad20)") (class "Default")
      (node (ref "U4") (pin "20") (pinfunction "NC_20") (pintype "passive"))
    )
    (net (code "76") (name "unconnected-(U4-NC-Pad21)") (class "Default")
      (node (ref "U4") (pin "21") (pinfunction "NC_21") (pintype "passive"))
    )
    (net (code "77") (name "unconnected-(U4-NC-Pad22)") (class "Default")
      (node (ref "U4") (pin "22") (pinfunction "NC_22") (pintype "passive"))
    )
    (net (code "78") (name "unconnected-(U4-NC{slash}VPP-Pad18)") (class "Default")
      (node (ref "U4") (pin "18") (pinfunction "NC/VPP_18") (pintype "passive"))
    )
    (net (code "79") (name "unconnected-(U4-RI-Pad2)") (class "Default")
      (node (ref "U4") (pin "2") (pinfunction "RI_2") (pintype "passive"))
    )
    (net (code "80") (name "unconnected-(U4-RST#-Pad9)") (class "Default")
      (node (ref "U4") (pin "9") (pinfunction "RST#_9") (pintype "passive"))
    )
    (net (code "81") (name "unconnected-(U4-SUSPEND#-Pad11)") (class "Default")
      (node (ref "U4") (pin "11") (pinfunction "SUSPEND#_11") (pintype "passive"))
    )
    (net (code "82") (name "unconnected-(U4-SUSPEND-Pad12)") (class "Default")
      (node (ref "U4") (pin "12") (pinfunction "SUSPEND_12") (pintype "passive"))
    )
    (net (code "83") (name "unconnected-(U4-VDD-Pad6)") (class "Default")
      (node (ref "U4") (pin "6") (pinfunction "VDD_6") (pintype "passive"))
    )
    (net (code "84") (name "unconnected-(USB1-CC1-PadA5)") (class "Default")
      (node (ref "USB1") (pin "A5") (pinfunction "CC1_A5") (pintype "passive"))
    )
    (net (code "85") (name "unconnected-(USB1-CC2-PadB5)") (class "Default")
      (node (ref "USB1") (pin "B5") (pinfunction "CC2_B5") (pintype "passive"))
    )
    (net (code "86") (name "unconnected-(USB1-SBU1-PadA8)") (class "Default")
      (node (ref "USB1") (pin "A8") (pinfunction "SBU1_A8") (pintype "passive"))
    )
    (net (code "87") (name "unconnected-(USB1-SBU2-PadB8)") (class "Default")
      (node (ref "USB1") (pin "B8") (pinfunction "SBU2_B8") (pintype "passive"))
    )
  )
)
